# Main.net
KiCad netlist of a schematic drawn in Altium Designer
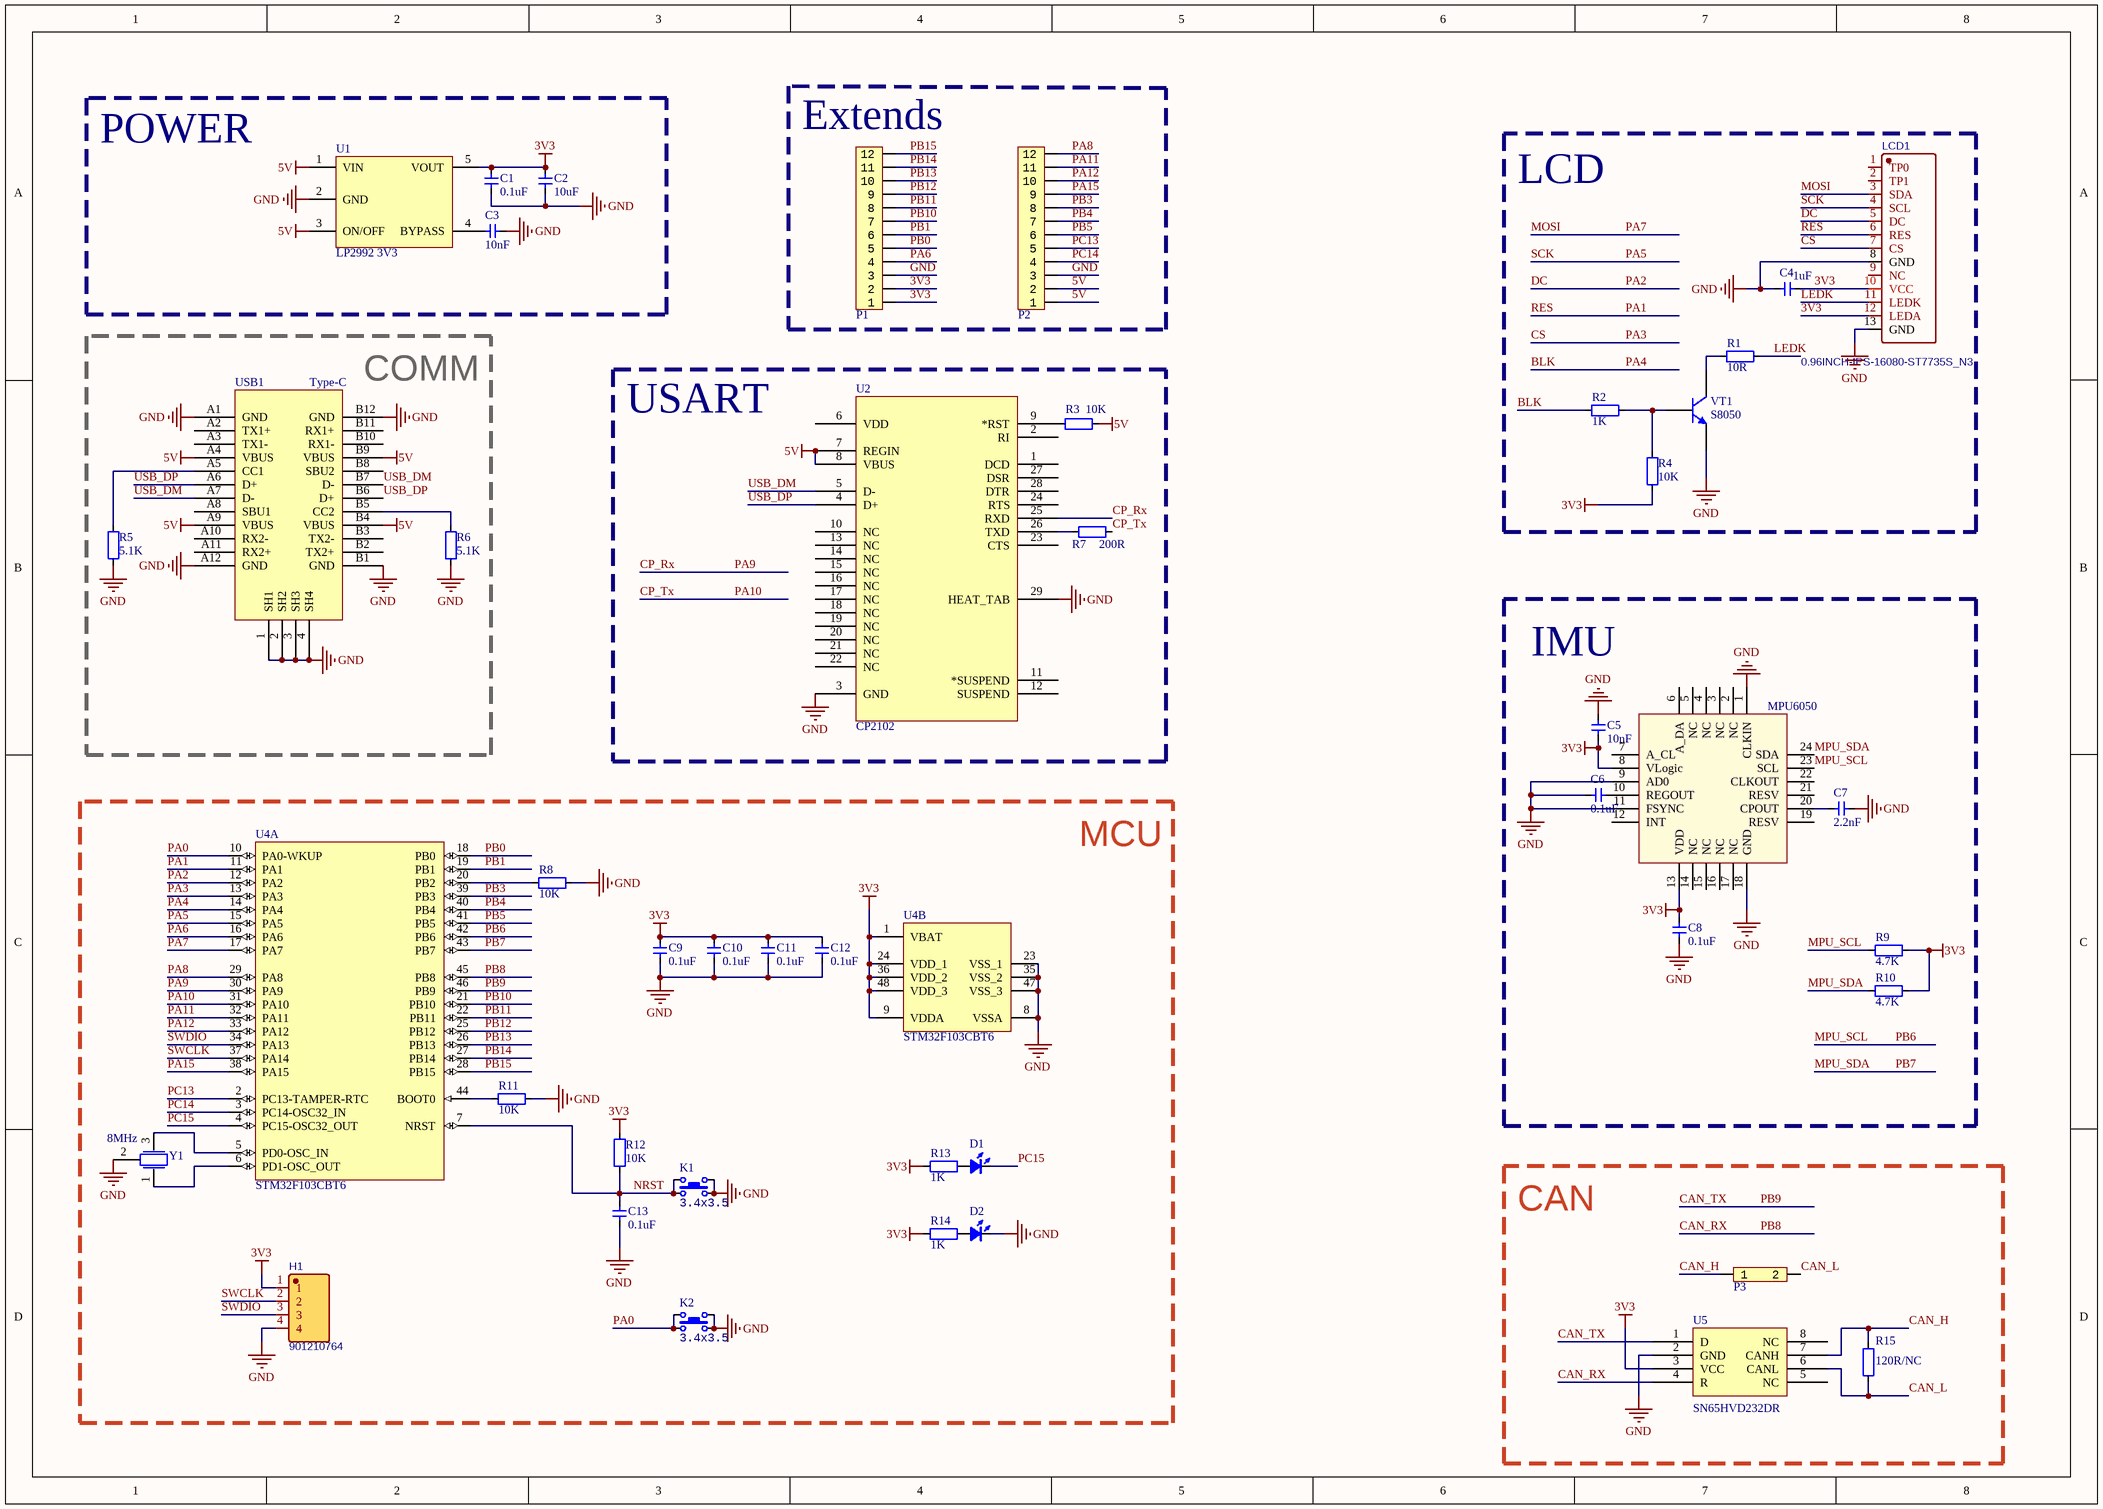
[diagram p0: Main.SchDoc]

(export (version "E")
  (design (tool "Eeschema 10.0.6"))
  (components
    (comp (ref "C1")
      (value "0.1uF")
      (footprint "CAP_0402")
      (description "Capacitor")
      (libsource (lib "MyPcbLib") (part "电容-0402"))
    )
    (comp (ref "C2")
      (value "10uF")
      (footprint "CAP_0402")
      (description "Capacitor")
      (libsource (lib "MyPcbLib") (part "电容-0402"))
    )
    (comp (ref "C3")
      (value "10nF")
      (footprint "CAP_0402")
      (description "Capacitor")
      (libsource (lib "MyPcbLib") (part "电容-0402"))
    )
    (comp (ref "C4")
      (value "1uF")
      (footprint "CAP_0402")
      (description "Capacitor")
      (libsource (lib "MyPcbLib") (part "电容-0402"))
    )
    (comp (ref "C5")
      (value "10nF")
      (footprint "CAP_0402")
      (description "Capacitor")
      (libsource (lib "MyPcbLib") (part "电容-0402"))
    )
    (comp (ref "C6")
      (value "0.1uF")
      (footprint "CAP_0402")
      (description "Capacitor")
      (libsource (lib "MyPcbLib") (part "电容-0402"))
    )
    (comp (ref "C7")
      (value "2.2nF")
      (footprint "CAP_0402")
      (description "Capacitor")
      (libsource (lib "MyPcbLib") (part "电容-0402"))
    )
    (comp (ref "C8")
      (value "0.1uF")
      (footprint "CAP_0402")
      (description "Capacitor")
      (libsource (lib "MyPcbLib") (part "电容-0402"))
    )
    (comp (ref "C9")
      (value "0.1uF")
      (footprint "CAP_0402")
      (description "Capacitor")
      (libsource (lib "MyPcbLib") (part "电容-0402"))
    )
    (comp (ref "C10")
      (value "0.1uF")
      (footprint "CAP_0402")
      (description "Capacitor")
      (libsource (lib "MyPcbLib") (part "电容-0402"))
    )
    (comp (ref "C11")
      (value "0.1uF")
      (footprint "CAP_0402")
      (description "Capacitor")
      (libsource (lib "MyPcbLib") (part "电容-0402"))
    )
    (comp (ref "C12")
      (value "0.1uF")
      (footprint "CAP_0402")
      (description "Capacitor")
      (libsource (lib "MyPcbLib") (part "电容-0402"))
    )
    (comp (ref "C13")
      (value "0.1uF")
      (footprint "CAP_0402")
      (description "Capacitor")
      (libsource (lib "MyPcbLib") (part "电容-0402"))
    )
    (comp (ref "D1")
      (value "color?")
      (footprint "LED_0402_RED")
      (description "LED")
      (libsource (lib "KitSprout") (part "LED_0402"))
    )
    (comp (ref "D2")
      (value "color?")
      (footprint "LED_0402_RED")
      (description "LED")
      (libsource (lib "KitSprout") (part "LED_0402"))
    )
    (comp (ref "H1")
      (value "901210764")
      (footprint "HDR-TH_4P-P2.54-H-M-W11.0")
      (fields (field (name "BOM_SUPPLIER PART") "C293357") (field (name "CONTRIBUTOR") "LCSC"))
      (libsource (lib "1_4P Hor") (part "901210764"))
    )
    (comp (ref "K1")
      (value "3.4x3.5")
      (footprint "ButtonTACT_3.5*3.55_90")
      (description "Button")
      (fields (field (name "Comment") "TACT 4P"))
      (libsource (lib "KitSprout") (part "ButtonTACT"))
    )
    (comp (ref "K2")
      (value "3.4x3.5")
      (footprint "ButtonTACT_3.5*3.55_90")
      (description "Button")
      (fields (field (name "Comment") "TACT 4P"))
      (libsource (lib "KitSprout") (part "ButtonTACT"))
    )
    (comp (ref "LCD1")
      (value "0.96INCH-IPS-16080-ST7735S_N3")
      (footprint "LCD-0.96INCH-IPS-TFT-16080-ST7735S")
      (fields (field (name "CONTRIBUTOR") "micespring"))
      (libsource (lib "0.96 TFT") (part "0.96INCH-IPS-16080-ST7735S_N3"))
    )
    (comp (ref "P1")
      (value "HDR1x12_2.54")
      (footprint "HDR1X12_2.54_180")
      (description "Header")
      (libsource (lib "KitSprout") (part "HDR1x12_2.54"))
    )
    (comp (ref "P2")
      (value "HDR1x12_2.54")
      (footprint "HDR1X12_2.54_180")
      (description "Header")
      (libsource (lib "KitSprout") (part "HDR1x12_2.54"))
    )
    (comp (ref "P3")
      (value "HDR2x1_2.54")
      (footprint "HDR1X2_2.54_180")
      (description "Header")
      (libsource (lib "KitSprout") (part "HDR2x1_2.54"))
    )
    (comp (ref "R1")
      (value "10R")
      (footprint "RES_0402")
      (description "Resistor")
      (libsource (lib "MyPcbLib") (part "电阻-0402"))
    )
    (comp (ref "R2")
      (value "1K")
      (footprint "RES_0402")
      (description "Resistor")
      (libsource (lib "MyPcbLib") (part "电阻-0402"))
    )
    (comp (ref "R3")
      (value "10K")
      (footprint "RES_0402")
      (description "Resistor")
      (libsource (lib "") (part "电阻-0402_1"))
    )
    (comp (ref "R4")
      (value "10K")
      (footprint "RES_0402")
      (description "Resistor")
      (libsource (lib "") (part "电阻-0402_3"))
    )
    (comp (ref "R5")
      (value "5.1K")
      (footprint "RES_0402")
      (description "Resistor")
      (libsource (lib "") (part "电阻-0402_2"))
    )
    (comp (ref "R6")
      (value "5.1K")
      (footprint "RES_0402")
      (description "Resistor")
      (libsource (lib "") (part "电阻-0402_2"))
    )
    (comp (ref "R7")
      (value "200R")
      (footprint "RES_0402")
      (description "Resistor")
      (libsource (lib "") (part "电阻-0402_1"))
    )
    (comp (ref "R8")
      (value "10K")
      (footprint "RES_0402")
      (description "Resistor")
      (libsource (lib "") (part "电阻-0402_1"))
    )
    (comp (ref "R9")
      (value "4.7K")
      (footprint "RES_0402")
      (description "Resistor")
      (libsource (lib "MyPcbLib") (part "电阻-0402"))
    )
    (comp (ref "R10")
      (value "4.7K")
      (footprint "RES_0402")
      (description "Resistor")
      (libsource (lib "MyPcbLib") (part "电阻-0402"))
    )
    (comp (ref "R11")
      (value "10K")
      (footprint "RES_0402")
      (description "Resistor")
      (libsource (lib "") (part "电阻-0402_1"))
    )
    (comp (ref "R12")
      (value "10K")
      (footprint "RES_0402")
      (description "Resistor")
      (libsource (lib "") (part "电阻-0402_3"))
    )
    (comp (ref "R13")
      (value "1K")
      (footprint "RES_0402")
      (description "Resistor")
      (libsource (lib "MyPcbLib") (part "电阻-0402"))
    )
    (comp (ref "R14")
      (value "1K")
      (footprint "RES_0402")
      (description "Resistor")
      (libsource (lib "MyPcbLib") (part "电阻-0402"))
    )
    (comp (ref "R15")
      (value "120R/NC")
      (footprint "RES_0402")
      (description "Resistor")
      (libsource (lib "") (part "电阻-0402_2"))
    )
    (comp (ref "U1")
      (value "LP2992 3V3")
      (footprint "SOT23-5")
      (description "LDO")
      (libsource (lib "MyPcbLib") (part "LP2992"))
    )
    (comp (ref "U2")
      (value "CP2102")
      (footprint "QFN-28")
      (description "USB转TTL")
      (libsource (lib "mLib") (part "CP2102"))
    )
    (comp (ref "U3")
      (value "MPU6050")
      (footprint "QFN-24")
      (description "六轴传感器")
      (libsource (lib "mLib") (part "MPU6050"))
    )
    (comp (ref "U4")
      (value "STM32F103CBT6")
      (footprint "LQFP-48")
      (libsource (lib "STMicroelectronics STM32 F1") (part "STM32F103CBT6"))
    )
    (comp (ref "U5")
      (value "SN65HVD232D")
      (footprint "SO-8")
      (fields
        (field (name "MANUFACTURER") "Texas Instruments")
        (field (name "MANUFACTURER PART NUMBER") "SN65HVD232DR")
      )
      (libsource (lib "MyPcbLib") (part "SN65HVD232D"))
    )
    (comp (ref "USB1")
      (value "Type-C")
      (footprint "Type-C-TOP")
      (libsource (lib "MyPcbLib") (part "USB-Type-C-TOP"))
    )
    (comp (ref "VT1")
      (value "S8050")
      (footprint "SMT_TRIODE_NPN")
      (description "Surface mount NPN transistor, package SOT-23")
      (libsource (lib "MyPcbLib") (part "SMT_TRIODE_NPN"))
    )
    (comp (ref "Y1")
      (value "8MHz")
      (footprint "晶振-3P")
      (description "村田贴片")
      (libsource (lib "MyPcbLib") (part "晶振-3Pin"))
    )
  )
  (nets
    (net (code "1") (name "/BLK") (class "Default")
      (node (ref "R2") (pin "1") (pinfunction "1_1") (pintype "passive"))
      (node (ref "U4") (pin "14") (pinfunction "PA4_14") (pintype "bidirectional"))
    )
    (net (code "2") (name "/CAN_H") (class "Default")
      (node (ref "P3") (pin "1") (pinfunction "1_1") (pintype "passive"))
      (node (ref "R15") (pin "1") (pinfunction "1_1") (pintype "passive"))
      (node (ref "U5") (pin "7") (pinfunction "CANH_7") (pintype "passive"))
    )
    (net (code "3") (name "/CAN_L") (class "Default")
      (node (ref "P3") (pin "2") (pinfunction "2_2") (pintype "passive"))
      (node (ref "R15") (pin "2") (pinfunction "2_2") (pintype "passive"))
      (node (ref "U5") (pin "6") (pinfunction "CANL_6") (pintype "passive"))
    )
    (net (code "4") (name "/CAN_RX") (class "Default")
      (node (ref "U4") (pin "45") (pinfunction "PB8_45") (pintype "bidirectional"))
      (node (ref "U5") (pin "4") (pinfunction "R_4") (pintype "passive"))
    )
    (net (code "5") (name "/CAN_TX") (class "Default")
      (node (ref "U4") (pin "46") (pinfunction "PB9_46") (pintype "bidirectional"))
      (node (ref "U5") (pin "1") (pinfunction "D_1") (pintype "passive"))
    )
    (net (code "6") (name "/CP_Rx") (class "Default")
      (node (ref "U2") (pin "25") (pinfunction "RXD_25") (pintype "passive"))
      (node (ref "U4") (pin "30") (pinfunction "PA9_30") (pintype "bidirectional"))
    )
    (net (code "7") (name "/CP_Tx") (class "Default")
      (node (ref "R7") (pin "1") (pinfunction "1_1") (pintype "passive"))
      (node (ref "U4") (pin "31") (pinfunction "PA10_31") (pintype "bidirectional"))
    )
    (net (code "8") (name "/CS") (class "Default")
      (node (ref "LCD1") (pin "7") (pinfunction "CS_7") (pintype "passive"))
      (node (ref "U4") (pin "13") (pinfunction "PA3_13") (pintype "bidirectional"))
    )
    (net (code "9") (name "/DC") (class "Default")
      (node (ref "LCD1") (pin "5") (pinfunction "DC_5") (pintype "passive"))
      (node (ref "U4") (pin "12") (pinfunction "PA2_12") (pintype "bidirectional"))
    )
    (net (code "10") (name "/LEDK") (class "Default")
      (node (ref "LCD1") (pin "11") (pinfunction "LEDK_11") (pintype "passive"))
      (node (ref "R1") (pin "2") (pinfunction "2_2") (pintype "passive"))
    )
    (net (code "11") (name "/MOSI") (class "Default")
      (node (ref "LCD1") (pin "3") (pinfunction "SDA_3") (pintype "passive"))
      (node (ref "U4") (pin "17") (pinfunction "PA7_17") (pintype "bidirectional"))
    )
    (net (code "12") (name "/MPU_SCL") (class "Default")
      (node (ref "R9") (pin "1") (pinfunction "1_1") (pintype "passive"))
      (node (ref "U3") (pin "23") (pinfunction "SCL_23") (pintype "passive"))
      (node (ref "U4") (pin "42") (pinfunction "PB6_42") (pintype "bidirectional"))
    )
    (net (code "13") (name "/MPU_SDA") (class "Default")
      (node (ref "R10") (pin "1") (pinfunction "1_1") (pintype "passive"))
      (node (ref "U3") (pin "24") (pinfunction "SDA_24") (pintype "passive"))
      (node (ref "U4") (pin "43") (pinfunction "PB7_43") (pintype "bidirectional"))
    )
    (net (code "14") (name "/NRST") (class "Default")
      (node (ref "C13") (pin "2") (pinfunction "2_2") (pintype "passive"))
      (node (ref "K1") (pin "1") (pinfunction "1_1") (pintype "passive"))
      (node (ref "K1") (pin "3") (pinfunction "3_3") (pintype "passive"))
      (node (ref "R12") (pin "1") (pinfunction "1_1") (pintype "passive"))
      (node (ref "U4") (pin "7") (pinfunction "NRST_7") (pintype "bidirectional"))
    )
    (net (code "15") (name "/PA0") (class "Default")
      (node (ref "K2") (pin "1") (pinfunction "1_1") (pintype "passive"))
      (node (ref "K2") (pin "3") (pinfunction "3_3") (pintype "passive"))
      (node (ref "U4") (pin "10") (pinfunction "PA0-WKUP_10") (pintype "bidirectional"))
    )
    (net (code "16") (name "/PA1") (class "Default")
      (node (ref "LCD1") (pin "6") (pinfunction "RES_6") (pintype "passive"))
      (node (ref "U4") (pin "11") (pinfunction "PA1_11") (pintype "bidirectional"))
    )
    (net (code "17") (name "/PA5") (class "Default")
      (node (ref "LCD1") (pin "4") (pinfunction "SCL_4") (pintype "passive"))
      (node (ref "U4") (pin "15") (pinfunction "PA5_15") (pintype "bidirectional"))
    )
    (net (code "18") (name "/PA6") (class "Default")
      (node (ref "P1") (pin "4") (pinfunction "4_4") (pintype "passive"))
      (node (ref "U4") (pin "16") (pinfunction "PA6_16") (pintype "bidirectional"))
    )
    (net (code "19") (name "/PA8") (class "Default")
      (node (ref "P2") (pin "12") (pinfunction "12_12") (pintype "passive"))
      (node (ref "U4") (pin "29") (pinfunction "PA8_29") (pintype "bidirectional"))
    )
    (net (code "20") (name "/PA11") (class "Default")
      (node (ref "P2") (pin "11") (pinfunction "11_11") (pintype "passive"))
      (node (ref "U4") (pin "32") (pinfunction "PA11_32") (pintype "bidirectional"))
    )
    (net (code "21") (name "/PA12") (class "Default")
      (node (ref "P2") (pin "10") (pinfunction "10_10") (pintype "passive"))
      (node (ref "U4") (pin "33") (pinfunction "PA12_33") (pintype "bidirectional"))
    )
    (net (code "22") (name "/PA15") (class "Default")
      (node (ref "P2") (pin "9") (pinfunction "9_9") (pintype "passive"))
      (node (ref "U4") (pin "38") (pinfunction "PA15_38") (pintype "bidirectional"))
    )
    (net (code "23") (name "/PB0") (class "Default")
      (node (ref "P1") (pin "5") (pinfunction "5_5") (pintype "passive"))
      (node (ref "U4") (pin "18") (pinfunction "PB0_18") (pintype "bidirectional"))
    )
    (net (code "24") (name "/PB1") (class "Default")
      (node (ref "P1") (pin "6") (pinfunction "6_6") (pintype "passive"))
      (node (ref "U4") (pin "19") (pinfunction "PB1_19") (pintype "bidirectional"))
    )
    (net (code "25") (name "/PB3") (class "Default")
      (node (ref "P2") (pin "8") (pinfunction "8_8") (pintype "passive"))
      (node (ref "U4") (pin "39") (pinfunction "PB3_39") (pintype "bidirectional"))
    )
    (net (code "26") (name "/PB4") (class "Default")
      (node (ref "P2") (pin "7") (pinfunction "7_7") (pintype "passive"))
      (node (ref "U4") (pin "40") (pinfunction "PB4_40") (pintype "bidirectional"))
    )
    (net (code "27") (name "/PB5") (class "Default")
      (node (ref "P2") (pin "6") (pinfunction "6_6") (pintype "passive"))
      (node (ref "U4") (pin "41") (pinfunction "PB5_41") (pintype "bidirectional"))
    )
    (net (code "28") (name "/PB10") (class "Default")
      (node (ref "P1") (pin "7") (pinfunction "7_7") (pintype "passive"))
      (node (ref "U4") (pin "21") (pinfunction "PB10_21") (pintype "bidirectional"))
    )
    (net (code "29") (name "/PB11") (class "Default")
      (node (ref "P1") (pin "8") (pinfunction "8_8") (pintype "passive"))
      (node (ref "U4") (pin "22") (pinfunction "PB11_22") (pintype "bidirectional"))
    )
    (net (code "30") (name "/PB12") (class "Default")
      (node (ref "P1") (pin "9") (pinfunction "9_9") (pintype "passive"))
      (node (ref "U4") (pin "25") (pinfunction "PB12_25") (pintype "bidirectional"))
    )
    (net (code "31") (name "/PB13") (class "Default")
      (node (ref "P1") (pin "10") (pinfunction "10_10") (pintype "passive"))
      (node (ref "U4") (pin "26") (pinfunction "PB13_26") (pintype "bidirectional"))
    )
    (net (code "32") (name "/PB14") (class "Default")
      (node (ref "P1") (pin "11") (pinfunction "11_11") (pintype "passive"))
      (node (ref "U4") (pin "27") (pinfunction "PB14_27") (pintype "bidirectional"))
    )
    (net (code "33") (name "/PB15") (class "Default")
      (node (ref "P1") (pin "12") (pinfunction "12_12") (pintype "passive"))
      (node (ref "U4") (pin "28") (pinfunction "PB15_28") (pintype "bidirectional"))
    )
    (net (code "34") (name "/PC13") (class "Default")
      (node (ref "P2") (pin "5") (pinfunction "5_5") (pintype "passive"))
      (node (ref "U4") (pin "2") (pinfunction "PC13-TAMPER-RTC_2") (pintype "bidirectional"))
    )
    (net (code "35") (name "/PC14") (class "Default")
      (node (ref "P2") (pin "4") (pinfunction "4_4") (pintype "passive"))
      (node (ref "U4") (pin "3") (pinfunction "PC14-OSC32_IN_3") (pintype "bidirectional"))
    )
    (net (code "36") (name "/PC15") (class "Default")
      (node (ref "D1") (pin "2") (pinfunction "K_2") (pintype "passive"))
      (node (ref "U4") (pin "4") (pinfunction "PC15-OSC32_OUT_4") (pintype "bidirectional"))
    )
    (net (code "37") (name "/SWCLK") (class "Default")
      (node (ref "H1") (pin "2") (pinfunction "2_2") (pintype "passive"))
      (node (ref "U4") (pin "37") (pinfunction "PA14_37") (pintype "bidirectional"))
    )
    (net (code "38") (name "/SWDIO") (class "Default")
      (node (ref "H1") (pin "3") (pinfunction "3_3") (pintype "passive"))
      (node (ref "U4") (pin "34") (pinfunction "PA13_34") (pintype "bidirectional"))
    )
    (net (code "39") (name "/USB_DM") (class "Default")
      (node (ref "U2") (pin "5") (pinfunction "D-_5") (pintype "passive"))
      (node (ref "USB1") (pin "A7") (pinfunction "D-_A7") (pintype "passive"))
      (node (ref "USB1") (pin "B7") (pinfunction "D-_B7") (pintype "passive"))
    )
    (net (code "40") (name "/USB_DP") (class "Default")
      (node (ref "U2") (pin "4") (pinfunction "D+_4") (pintype "passive"))
      (node (ref "USB1") (pin "A6") (pinfunction "D+_A6") (pintype "passive"))
      (node (ref "USB1") (pin "B6") (pinfunction "D+_B6") (pintype "passive"))
    )
    (net (code "41") (name "3V3") (class "Default")
      (node (ref "C1") (pin "2") (pinfunction "2_2") (pintype "passive"))
      (node (ref "C10") (pin "2") (pinfunction "2_2") (pintype "passive"))
      (node (ref "C11") (pin "2") (pinfunction "2_2") (pintype "passive"))
      (node (ref "C12") (pin "2") (pinfunction "2_2") (pintype "passive"))
      (node (ref "C2") (pin "2") (pinfunction "2_2") (pintype "passive"))
      (node (ref "C4") (pin "1") (pinfunction "1_1") (pintype "passive"))
      (node (ref "C5") (pin "1") (pinfunction "1_1") (pintype "passive"))
      (node (ref "C8") (pin "2") (pinfunction "2_2") (pintype "passive"))
      (node (ref "C9") (pin "2") (pinfunction "2_2") (pintype "passive"))
      (node (ref "H1") (pin "1") (pinfunction "1_1") (pintype "passive"))
      (node (ref "LCD1") (pin "10") (pinfunction "VCC_10") (pintype "passive"))
      (node (ref "LCD1") (pin "12") (pinfunction "LEDA_12") (pintype "passive"))
      (node (ref "P1") (pin "1") (pinfunction "1_1") (pintype "passive"))
      (node (ref "P1") (pin "2") (pinfunction "2_2") (pintype "passive"))
      (node (ref "R10") (pin "2") (pinfunction "2_2") (pintype "passive"))
      (node (ref "R12") (pin "2") (pinfunction "2_2") (pintype "passive"))
      (node (ref "R13") (pin "1") (pinfunction "1_1") (pintype "passive"))
      (node (ref "R14") (pin "1") (pinfunction "1_1") (pintype "passive"))
      (node (ref "R4") (pin "1") (pinfunction "1_1") (pintype "passive"))
      (node (ref "R9") (pin "2") (pinfunction "2_2") (pintype "passive"))
      (node (ref "U1") (pin "5") (pinfunction "VOUT_5") (pintype "passive"))
      (node (ref "U3") (pin "13") (pinfunction "VDD_13") (pintype "passive"))
      (node (ref "U3") (pin "8") (pinfunction "VLogic_8") (pintype "passive"))
      (node (ref "U4") (pin "1") (pinfunction "VBAT_1") (pintype "power_in"))
      (node (ref "U4") (pin "24") (pinfunction "VDD_1_24") (pintype "power_in"))
      (node (ref "U4") (pin "36") (pinfunction "VDD_2_36") (pintype "power_in"))
      (node (ref "U4") (pin "48") (pinfunction "VDD_3_48") (pintype "power_in"))
      (node (ref "U4") (pin "9") (pinfunction "VDDA_9") (pintype "power_in"))
      (node (ref "U5") (pin "3") (pinfunction "VCC_3") (pintype "passive"))
    )
    (net (code "42") (name "5V") (class "Default")
      (node (ref "P2") (pin "1") (pinfunction "1_1") (pintype "passive"))
      (node (ref "P2") (pin "2") (pinfunction "2_2") (pintype "passive"))
      (node (ref "R3") (pin "1") (pinfunction "1_1") (pintype "passive"))
      (node (ref "U1") (pin "1") (pinfunction "VIN_1") (pintype "passive"))
      (node (ref "U1") (pin "3") (pinfunction "ON/OFF_3") (pintype "passive"))
      (node (ref "U2") (pin "7") (pinfunction "REGIN_7") (pintype "passive"))
      (node (ref "U2") (pin "8") (pinfunction "VBUS_8") (pintype "passive"))
      (node (ref "USB1") (pin "A4") (pinfunction "VBUS_A4") (pintype "passive"))
      (node (ref "USB1") (pin "A9") (pinfunction "VBUS_A9") (pintype "passive"))
      (node (ref "USB1") (pin "B4") (pinfunction "VBUS_B4") (pintype "passive"))
      (node (ref "USB1") (pin "B9") (pinfunction "VBUS_B9") (pintype "passive"))
    )
    (net (code "43") (name "GND") (class "Default")
      (node (ref "C1") (pin "1") (pinfunction "1_1") (pintype "passive"))
      (node (ref "C10") (pin "1") (pinfunction "1_1") (pintype "passive"))
      (node (ref "C11") (pin "1") (pinfunction "1_1") (pintype "passive"))
      (node (ref "C12") (pin "1") (pinfunction "1_1") (pintype "passive"))
      (node (ref "C13") (pin "1") (pinfunction "1_1") (pintype "passive"))
      (node (ref "C2") (pin "1") (pinfunction "1_1") (pintype "passive"))
      (node (ref "C3") (pin "1") (pinfunction "1_1") (pintype "passive"))
      (node (ref "C4") (pin "2") (pinfunction "2_2") (pintype "passive"))
      (node (ref "C5") (pin "2") (pinfunction "2_2") (pintype "passive"))
      (node (ref "C6") (pin "2") (pinfunction "2_2") (pintype "passive"))
      (node (ref "C7") (pin "1") (pinfunction "1_1") (pintype "passive"))
      (node (ref "C8") (pin "1") (pinfunction "1_1") (pintype "passive"))
      (node (ref "C9") (pin "1") (pinfunction "1_1") (pintype "passive"))
      (node (ref "D2") (pin "2") (pinfunction "K_2") (pintype "passive"))
      (node (ref "H1") (pin "4") (pinfunction "4_4") (pintype "passive"))
      (node (ref "K1") (pin "2") (pinfunction "2_2") (pintype "passive"))
      (node (ref "K1") (pin "4") (pinfunction "4_4") (pintype "passive"))
      (node (ref "K2") (pin "2") (pinfunction "2_2") (pintype "passive"))
      (node (ref "K2") (pin "4") (pinfunction "4_4") (pintype "passive"))
      (node (ref "LCD1") (pin "13") (pinfunction "GND_13") (pintype "passive"))
      (node (ref "LCD1") (pin "8") (pinfunction "GND_8") (pintype "passive"))
      (node (ref "P1") (pin "3") (pinfunction "3_3") (pintype "passive"))
      (node (ref "P2") (pin "3") (pinfunction "3_3") (pintype "passive"))
      (node (ref "R11") (pin "1") (pinfunction "1_1") (pintype "passive"))
      (node (ref "R5") (pin "2") (pinfunction "2_2") (pintype "passive"))
      (node (ref "R6") (pin "2") (pinfunction "2_2") (pintype "passive"))
      (node (ref "R8") (pin "1") (pinfunction "1_1") (pintype "passive"))
      (node (ref "U1") (pin "2") (pinfunction "GND_2") (pintype "passive"))
      (node (ref "U2") (pin "29") (pinfunction "HEAT_TAB_29") (pintype "passive"))
      (node (ref "U2") (pin "3") (pinfunction "GND_3") (pintype "passive"))
      (node (ref "U3") (pin "1") (pinfunction "CLKIN_1") (pintype "passive"))
      (node (ref "U3") (pin "11") (pinfunction "FSYNC_11") (pintype "passive"))
      (node (ref "U3") (pin "18") (pinfunction "GND_18") (pintype "passive"))
      (node (ref "U3") (pin "9") (pinfunction "AD0_9") (pintype "passive"))
      (node (ref "U4") (pin "23") (pinfunction "VSS_1_23") (pintype "power_in"))
      (node (ref "U4") (pin "35") (pinfunction "VSS_2_35") (pintype "power_in"))
      (node (ref "U4") (pin "47") (pinfunction "VSS_3_47") (pintype "power_in"))
      (node (ref "U4") (pin "8") (pinfunction "VSSA_8") (pintype "power_in"))
      (node (ref "U5") (pin "2") (pinfunction "GND_2") (pintype "passive"))
      (node (ref "USB1") (pin "1") (pinfunction "SH1_1") (pintype "passive"))
      (node (ref "USB1") (pin "2") (pinfunction "SH2_2") (pintype "passive"))
      (node (ref "USB1") (pin "3") (pinfunction "SH3_3") (pintype "passive"))
      (node (ref "USB1") (pin "4") (pinfunction "SH4_4") (pintype "passive"))
      (node (ref "USB1") (pin "A1") (pinfunction "GND_A1") (pintype "passive"))
      (node (ref "USB1") (pin "A12") (pinfunction "GND_A12") (pintype "passive"))
      (node (ref "USB1") (pin "B1") (pinfunction "GND_B1") (pintype "passive"))
      (node (ref "USB1") (pin "B12") (pinfunction "GND_B12") (pintype "passive"))
      (node (ref "VT1") (pin "2") (pinfunction "E_2") (pintype "passive"))
      (node (ref "Y1") (pin "2") (pinfunction "2_2") (pintype "passive"))
    )
    (net (code "44") (name "Net-(D1-A)") (class "Default")
      (node (ref "D1") (pin "1") (pinfunction "A_1") (pintype "passive"))
      (node (ref "R13") (pin "2") (pinfunction "2_2") (pintype "passive"))
    )
    (net (code "45") (name "Net-(D2-A)") (class "Default")
      (node (ref "D2") (pin "1") (pinfunction "A_1") (pintype "passive"))
      (node (ref "R14") (pin "2") (pinfunction "2_2") (pintype "passive"))
    )
    (net (code "46") (name "Net-(U1-BYPASS)") (class "Default")
      (node (ref "C3") (pin "2") (pinfunction "2_2") (pintype "passive"))
      (node (ref "U1") (pin "4") (pinfunction "BYPASS_4") (pintype "passive"))
    )
    (net (code "47") (name "Net-(U2-*RST)") (class "Default")
      (node (ref "R3") (pin "2") (pinfunction "2_2") (pintype "passive"))
      (node (ref "U2") (pin "9") (pinfunction "*RST_9") (pintype "passive"))
    )
    (net (code "48") (name "Net-(U2-TXD)") (class "Default")
      (node (ref "R7") (pin "2") (pinfunction "2_2") (pintype "passive"))
      (node (ref "U2") (pin "26") (pinfunction "TXD_26") (pintype "passive"))
    )
    (net (code "49") (name "Net-(U3-CPOUT)") (class "Default")
      (node (ref "C7") (pin "2") (pinfunction "2_2") (pintype "passive"))
      (node (ref "U3") (pin "20") (pinfunction "CPOUT_20") (pintype "passive"))
    )
    (net (code "50") (name "Net-(U3-REGOUT)") (class "Default")
      (node (ref "C6") (pin "1") (pinfunction "1_1") (pintype "passive"))
      (node (ref "U3") (pin "10") (pinfunction "REGOUT_10") (pintype "passive"))
    )
    (net (code "51") (name "Net-(U4A-BOOT0)") (class "Default")
      (node (ref "R11") (pin "2") (pinfunction "2_2") (pintype "passive"))
      (node (ref "U4") (pin "44") (pinfunction "BOOT0_44") (pintype "input"))
    )
    (net (code "52") (name "Net-(U4A-PB2)") (class "Default")
      (node (ref "R8") (pin "2") (pinfunction "2_2") (pintype "passive"))
      (node (ref "U4") (pin "20") (pinfunction "PB2_20") (pintype "bidirectional"))
    )
    (net (code "53") (name "Net-(U4A-PD0-OSC_IN)") (class "Default")
      (node (ref "U4") (pin "5") (pinfunction "PD0-OSC_IN_5") (pintype "bidirectional"))
      (node (ref "Y1") (pin "3") (pinfunction "3_3") (pintype "passive"))
    )
    (net (code "54") (name "Net-(U4A-PD1-OSC_OUT)") (class "Default")
      (node (ref "U4") (pin "6") (pinfunction "PD1-OSC_OUT_6") (pintype "bidirectional"))
      (node (ref "Y1") (pin "1") (pinfunction "1_1") (pintype "passive"))
    )
    (net (code "55") (name "Net-(USB1-CC1)") (class "Default")
      (node (ref "R5") (pin "1") (pinfunction "1_1") (pintype "passive"))
      (node (ref "USB1") (pin "A5") (pinfunction "CC1_A5") (pintype "passive"))
    )
    (net (code "56") (name "Net-(USB1-CC2)") (class "Default")
      (node (ref "R6") (pin "1") (pinfunction "1_1") (pintype "passive"))
      (node (ref "USB1") (pin "B5") (pinfunction "CC2_B5") (pintype "passive"))
    )
    (net (code "57") (name "Net-(VT1-B)") (class "Default")
      (node (ref "R2") (pin "2") (pinfunction "2_2") (pintype "passive"))
      (node (ref "R4") (pin "2") (pinfunction "2_2") (pintype "passive"))
      (node (ref "VT1") (pin "1") (pinfunction "B_1") (pintype "passive"))
    )
    (net (code "58") (name "Net-(VT1-C)") (class "Default")
      (node (ref "R1") (pin "1") (pinfunction "1_1") (pintype "passive"))
      (node (ref "VT1") (pin "3") (pinfunction "C_3") (pintype "passive"))
    )
    (net (code "59") (name "unconnected-(LCD1-NC-Pad9)") (class "Default")
      (node (ref "LCD1") (pin "9") (pinfunction "NC_9") (pintype "passive"))
    )
    (net (code "60") (name "unconnected-(LCD1-TP0-Pad1)") (class "Default")
      (node (ref "LCD1") (pin "1") (pinfunction "TP0_1") (pintype "passive"))
    )
    (net (code "61") (name "unconnected-(LCD1-TP1-Pad2)") (class "Default")
      (node (ref "LCD1") (pin "2") (pinfunction "TP1_2") (pintype "passive"))
    )
    (net (code "62") (name "unconnected-(U2-*SUSPEND-Pad11)") (class "Default")
      (node (ref "U2") (pin "11") (pinfunction "*SUSPEND_11") (pintype "passive"))
    )
    (net (code "63") (name "unconnected-(U2-CTS-Pad23)") (class "Default")
      (node (ref "U2") (pin "23") (pinfunction "CTS_23") (pintype "passive"))
    )
    (net (code "64") (name "unconnected-(U2-DCD-Pad1)") (class "Default")
      (node (ref "U2") (pin "1") (pinfunction "DCD_1") (pintype "passive"))
    )
    (net (code "65") (name "unconnected-(U2-DSR-Pad27)") (class "Default")
      (node (ref "U2") (pin "27") (pinfunction "DSR_27") (pintype "passive"))
    )
    (net (code "66") (name "unconnected-(U2-DTR-Pad28)") (class "Default")
      (node (ref "U2") (pin "28") (pinfunction "DTR_28") (pintype "passive"))
    )
    (net (code "67") (name "unconnected-(U2-NC-Pad10)") (class "Default")
      (node (ref "U2") (pin "10") (pinfunction "NC_10") (pintype "passive"))
    )
    (net (code "68") (name "unconnected-(U2-NC-Pad13)") (class "Default")
      (node (ref "U2") (pin "13") (pinfunction "NC_13") (pintype "passive"))
    )
    (net (code "69") (name "unconnected-(U2-NC-Pad14)") (class "Default")
      (node (ref "U2") (pin "14") (pinfunction "NC_14") (pintype "passive"))
    )
    (net (code "70") (name "unconnected-(U2-NC-Pad15)") (class "Default")
      (node (ref "U2") (pin "15") (pinfunction "NC_15") (pintype "passive"))
    )
    (net (code "71") (name "unconnected-(U2-NC-Pad16)") (class "Default")
      (node (ref "U2") (pin "16") (pinfunction "NC_16") (pintype "passive"))
    )
    (net (code "72") (name "unconnected-(U2-NC-Pad17)") (class "Default")
      (node (ref "U2") (pin "17") (pinfunction "NC_17") (pintype "passive"))
    )
    (net (code "73") (name "unconnected-(U2-NC-Pad18)") (class "Default")
      (node (ref "U2") (pin "18") (pinfunction "NC_18") (pintype "passive"))
    )
    (net (code "74") (name "unconnected-(U2-NC-Pad19)") (class "Default")
      (node (ref "U2") (pin "19") (pinfunction "NC_19") (pintype "passive"))
    )
    (net (code "75") (name "unconnected-(U2-NC-Pad20)") (class "Default")
      (node (ref "U2") (pin "20") (pinfunction "NC_20") (pintype "passive"))
    )
    (net (code "76") (name "unconnected-(U2-NC-Pad21)") (class "Default")
      (node (ref "U2") (pin "21") (pinfunction "NC_21") (pintype "passive"))
    )
    (net (code "77") (name "unconnected-(U2-NC-Pad22)") (class "Default")
      (node (ref "U2") (pin "22") (pinfunction "NC_22") (pintype "passive"))
    )
    (net (code "78") (name "unconnected-(U2-RI-Pad2)") (class "Default")
      (node (ref "U2") (pin "2") (pinfunction "RI_2") (pintype "passive"))
    )
    (net (code "79") (name "unconnected-(U2-RTS-Pad24)") (class "Default")
      (node (ref "U2") (pin "24") (pinfunction "RTS_24") (pintype "passive"))
    )
    (net (code "80") (name "unconnected-(U2-SUSPEND-Pad12)") (class "Default")
      (node (ref "U2") (pin "12") (pinfunction "SUSPEND_12") (pintype "passive"))
    )
    (net (code "81") (name "unconnected-(U2-VDD-Pad6)") (class "Default")
      (node (ref "U2") (pin "6") (pinfunction "VDD_6") (pintype "passive"))
    )
    (net (code "82") (name "unconnected-(U3-A_CL-Pad7)") (class "Default")
      (node (ref "U3") (pin "7") (pinfunction "A_CL_7") (pintype "passive"))
    )
    (net (code "83") (name "unconnected-(U3-A_DA-Pad6)") (class "Default")
      (node (ref "U3") (pin "6") (pinfunction "A_DA_6") (pintype "passive"))
    )
    (net (code "84") (name "unconnected-(U3-CLKOUT-Pad22)") (class "Default")
      (node (ref "U3") (pin "22") (pinfunction "CLKOUT_22") (pintype "passive"))
    )
    (net (code "85") (name "unconnected-(U3-INT-Pad12)") (class "Default")
      (node (ref "U3") (pin "12") (pinfunction "INT_12") (pintype "passive"))
    )
    (net (code "86") (name "unconnected-(U3-NC-Pad2)") (class "Default")
      (node (ref "U3") (pin "2") (pinfunction "NC_2") (pintype "passive"))
    )
    (net (code "87") (name "unconnected-(U3-NC-Pad3)") (class "Default")
      (node (ref "U3") (pin "3") (pinfunction "NC_3") (pintype "passive"))
    )
    (net (code "88") (name "unconnected-(U3-NC-Pad4)") (class "Default")
      (node (ref "U3") (pin "4") (pinfunction "NC_4") (pintype "passive"))
    )
    (net (code "89") (name "unconnected-(U3-NC-Pad5)") (class "Default")
      (node (ref "U3") (pin "5") (pinfunction "NC_5") (pintype "passive"))
    )
    (net (code "90") (name "unconnected-(U3-NC-Pad14)") (class "Default")
      (node (ref "U3") (pin "14") (pinfunction "NC_14") (pintype "passive"))
    )
    (net (code "91") (name "unconnected-(U3-NC-Pad15)") (class "Default")
      (node (ref "U3") (pin "15") (pinfunction "NC_15") (pintype "passive"))
    )
    (net (code "92") (name "unconnected-(U3-NC-Pad16)") (class "Default")
      (node (ref "U3") (pin "16") (pinfunction "NC_16") (pintype "passive"))
    )
    (net (code "93") (name "unconnected-(U3-NC-Pad17)") (class "Default")
      (node (ref "U3") (pin "17") (pinfunction "NC_17") (pintype "passive"))
    )
    (net (code "94") (name "unconnected-(U3-RESV-Pad19)") (class "Default")
      (node (ref "U3") (pin "19") (pinfunction "RESV_19") (pintype "passive"))
    )
    (net (code "95") (name "unconnected-(U3-RESV-Pad21)") (class "Default")
      (node (ref "U3") (pin "21") (pinfunction "RESV_21") (pintype "passive"))
    )
    (net (code "96") (name "unconnected-(U5-NC-Pad5)") (class "Default")
      (node (ref "U5") (pin "5") (pinfunction "NC_5") (pintype "passive"))
    )
    (net (code "97") (name "unconnected-(U5-NC-Pad8)") (class "Default")
      (node (ref "U5") (pin "8") (pinfunction "NC_8") (pintype "passive"))
    )
    (net (code "98") (name "unconnected-(USB1-RX1+-PadB11)") (class "Default")
      (node (ref "USB1") (pin "B11") (pinfunction "RX1+_B11") (pintype "passive"))
    )
    (net (code "99") (name "unconnected-(USB1-RX1--PadB10)") (class "Default")
      (node (ref "USB1") (pin "B10") (pinfunction "RX1-_B10") (pintype "passive"))
    )
    (net (code "100") (name "unconnected-(USB1-RX2+-PadA11)") (class "Default")
      (node (ref "USB1") (pin "A11") (pinfunction "RX2+_A11") (pintype "passive"))
    )
    (net (code "101") (name "unconnected-(USB1-RX2--PadA10)") (class "Default")
      (node (ref "USB1") (pin "A10") (pinfunction "RX2-_A10") (pintype "passive"))
    )
    (net (code "102") (name "unconnected-(USB1-SBU1-PadA8)") (class "Default")
      (node (ref "USB1") (pin "A8") (pinfunction "SBU1_A8") (pintype "passive"))
    )
    (net (code "103") (name "unconnected-(USB1-SBU2-PadB8)") (class "Default")
      (node (ref "USB1") (pin "B8") (pinfunction "SBU2_B8") (pintype "passive"))
    )
    (net (code "104") (name "unconnected-(USB1-TX1+-PadA2)") (class "Default")
      (node (ref "USB1") (pin "A2") (pinfunction "TX1+_A2") (pintype "passive"))
    )
    (net (code "105") (name "unconnected-(USB1-TX1--PadA3)") (class "Default")
      (node (ref "USB1") (pin "A3") (pinfunction "TX1-_A3") (pintype "passive"))
    )
    (net (code "106") (name "unconnected-(USB1-TX2+-PadB2)") (class "Default")
      (node (ref "USB1") (pin "B2") (pinfunction "TX2+_B2") (pintype "passive"))
    )
    (net (code "107") (name "unconnected-(USB1-TX2--PadB3)") (class "Default")
      (node (ref "USB1") (pin "B3") (pinfunction "TX2-_B3") (pintype "passive"))
    )
  )
)
